# OTP3.net
KiCad netlist of a schematic drawn in Altium Designer
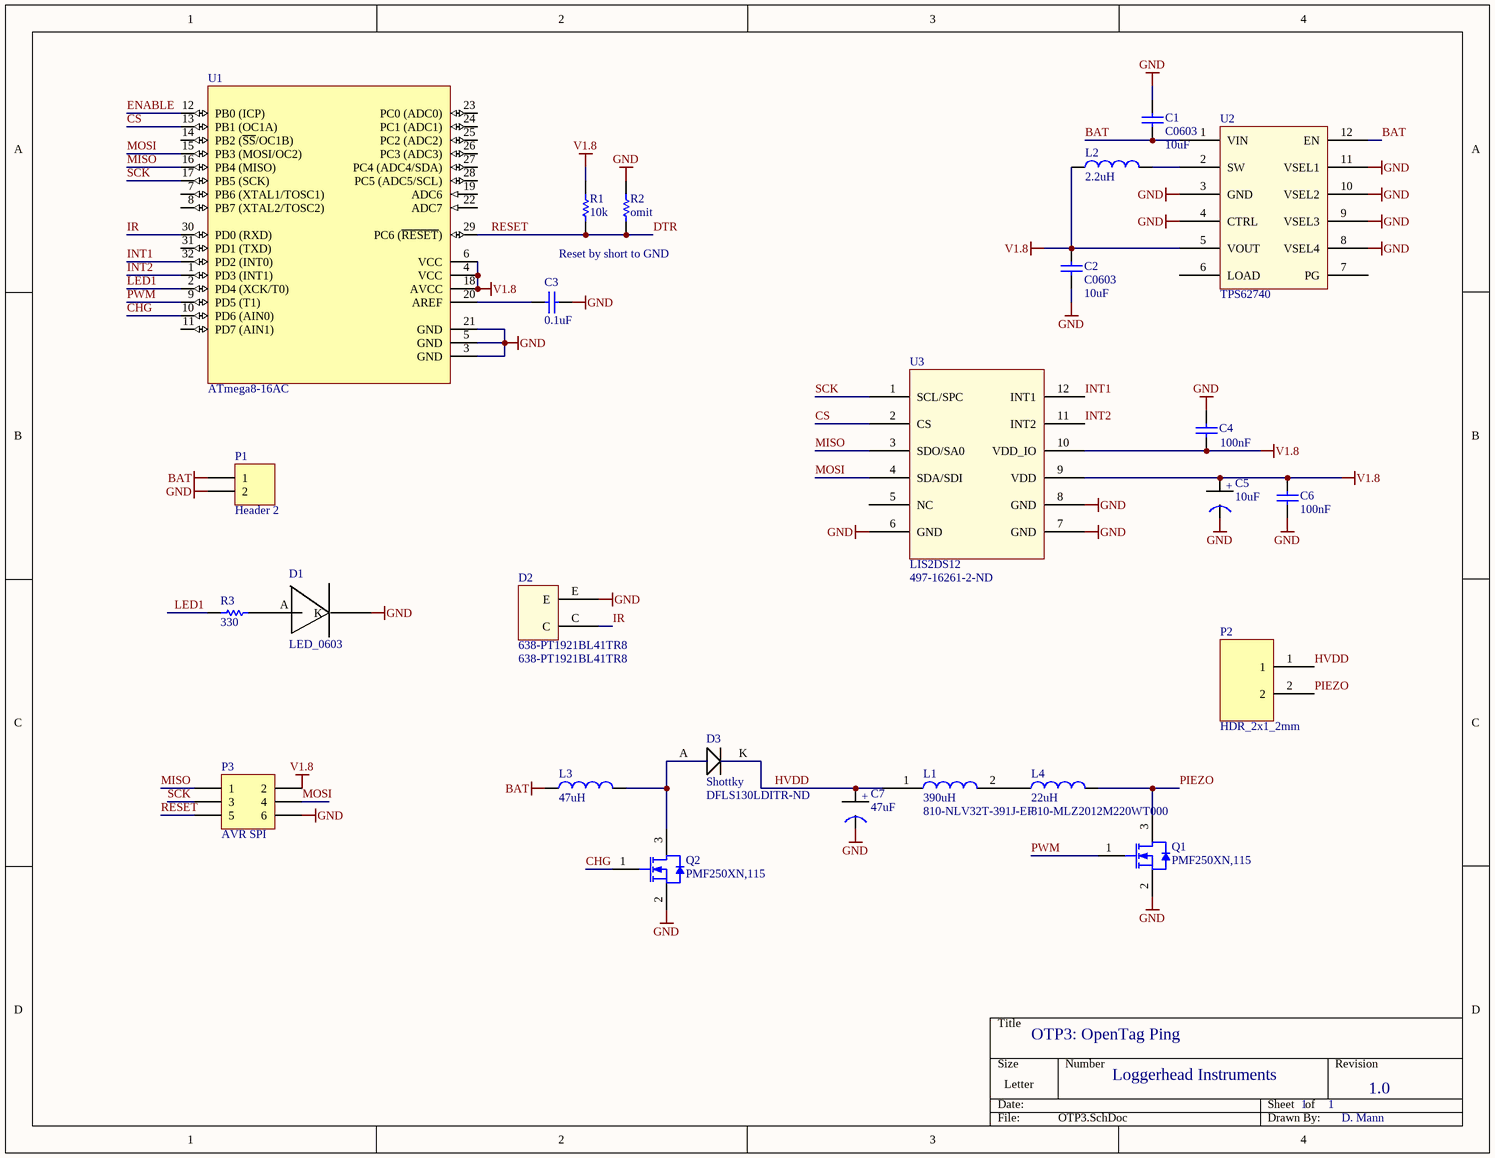
[diagram p0: OTP3.SchDoc]

(export (version "E")
  (design (tool "Eeschema 10.0.6"))
  (components
    (comp (ref "C1")
      (value "C0603")
      (footprint "0603")
      (description "Ceramic Chip Capacitor - Standard")
      (fields (field (name "ALTIUM_VALUE") "10uF") (field (name "PUBLISHER") "Altium Limited"))
      (libsource (lib "KEMET Chip Capacitor") (part "C0603"))
    )
    (comp (ref "C2")
      (value "C0603")
      (footprint "0603")
      (description "Ceramic Chip Capacitor - Standard")
      (fields (field (name "ALTIUM_VALUE") "10uF") (field (name "PUBLISHER") "Altium Limited"))
      (libsource (lib "KEMET Chip Capacitor") (part "C0603"))
    )
    (comp (ref "C3")
      (value "0.1uF")
      (footprint "0402")
      (description "Ceramic Chip Capacitor - Standard")
      (fields (field (name "PUBLISHER") "Altium Limited"))
      (libsource (lib "KEMET Chip Capacitor") (part "C0402"))
    )
    (comp (ref "C4")
      (value "100nF")
      (footprint "0402")
      (description "Ceramic Chip Capacitor - Standard")
      (fields (field (name "PUBLISHER") "Altium Limited"))
      (libsource (lib "KEMET Chip Capacitor") (part "C0402"))
    )
    (comp (ref "C5") (value "10uF") (footprint "Tant0805") (libsource (lib "Loggerhead") (part "Tant0805")))
    (comp (ref "C6")
      (value "100nF")
      (footprint "0402")
      (description "Ceramic Chip Capacitor - Standard")
      (fields (field (name "PUBLISHER") "Altium Limited"))
      (libsource (lib "KEMET Chip Capacitor") (part "C0402"))
    )
    (comp (ref "C7") (value "47uF") (footprint "Tant0805") (libsource (lib "Loggerhead") (part "Tant0805")))
    (comp (ref "D1")
      (value "LED_0603")
      (footprint "Diode0603")
      (libsource (lib "Loggerhead") (part "LED_0603"))
    )
    (comp (ref "D2")
      (value "638-PT1921BL41TR8")
      (footprint "Phototransistor")
      (description "Phototransistor")
      (fields (field (name "SUPPLIER PART NUMBER 1") "638-PT1921BL41TR8"))
      (libsource (lib "Loggerhead") (part "Phototransistor"))
    )
    (comp (ref "D3")
      (value "Shottky")
      (footprint "DFLS130")
      (fields (field (name "SUPPLIER PART NUMBER 1") "DFLS130LDITR-ND"))
      (libsource (lib "Loggerhead") (part "DFLS130"))
    )
    (comp (ref "L1")
      (value "390uH")
      (footprint "Inductor_NLV32T")
      (fields (field (name "SUPPLIER PART NUMBER 1") "810-NLV32T-391J-EF"))
      (libsource (lib "Loggerhead") (part "Inductor_NLV32T"))
    )
    (comp (ref "L2")
      (value "2.2uH")
      (footprint "Inductor KLZ1608AHR")
      (libsource (lib "Loggerhead") (part "Inductor KLZ1608"))
    )
    (comp (ref "L3")
      (value "47uH")
      (footprint "Inductor KLZ1608AHR")
      (libsource (lib "Loggerhead") (part "Inductor KLZ1608"))
    )
    (comp (ref "L4")
      (value "22uH")
      (footprint "Inductor MLZ2012M220WT000")
      (fields (field (name "SUPPLIER PART NUMBER 1") "810-MLZ2012M220WT000"))
      (libsource (lib "Loggerhead") (part "Inductor MLZ2012M220WT000"))
    )
    (comp (ref "P1")
      (value "Header 2")
      (footprint "HDR1X2")
      (description "Header, 2-Pin")
      (fields (field (name "PUBLISHER") "Altium Limited"))
      (libsource (lib "Miscellaneous Connectors") (part "Header 2"))
    )
    (comp (ref "P2")
      (value "HDR_2x1_2mm")
      (footprint "HDR_2x1_2mm")
      (libsource (lib "Loggerhead") (part "HDR_2x1_2mm"))
    )
    (comp (ref "P3")
      (value "AVR SPI")
      (footprint "HDR2X3")
      (description "Header, 3-Pin, Dual row")
      (fields (field (name "PUBLISHER") "Altium Limited"))
      (libsource (lib "Miscellaneous Connectors") (part "Header 3X2"))
    )
    (comp (ref "Q1")
      (value "PMF250XN,115")
      (footprint "NXP-SOT323_N")
      (description "N-Channel Trench MOSFET, 30 V, 0.9 A, -55 to 150 degC, 3-Pin SOT323, Tape and Reel")
      (fields (field (name "MANUFACTURER") "NXP Semiconductors"))
      (libsource (lib "NXP Semiconductors Standard MOSFETs") (part "PMF250XN,115"))
    )
    (comp (ref "Q2")
      (value "PMF250XN,115")
      (footprint "NXP-SOT323_N")
      (description "N-Channel Trench MOSFET, 30 V, 0.9 A, -55 to 150 degC, 3-Pin SOT323, Tape and Reel")
      (fields (field (name "MANUFACTURER") "NXP Semiconductors"))
      (libsource (lib "NXP Semiconductors Standard MOSFETs") (part "PMF250XN,115"))
    )
    (comp (ref "R1")
      (value "10k")
      (footprint "3-0603")
      (fields (field (name "PUBLISHER") "Altium Limited"))
      (libsource (lib "Panasonic Resistor") (part "ERJ3RK"))
    )
    (comp (ref "R2")
      (value "omit")
      (footprint "3-0603")
      (fields (field (name "PUBLISHER") "Altium Limited"))
      (libsource (lib "Panasonic Resistor") (part "ERJ3RK"))
    )
    (comp (ref "R3")
      (value "330")
      (footprint "3-0603")
      (fields (field (name "PUBLISHER") "Altium Limited"))
      (libsource (lib "Panasonic Resistor") (part "ERJ3RK"))
    )
    (comp (ref "U1")
      (value "ATmega8-16AC")
      (footprint "32M1-A_M")
      (description "8-Bit AVR Microcontroller with 8K Bytes of In-System Programmable Flash Memory")
      (fields (field (name "PUBLISHER") "Altium Limited"))
      (libsource (lib "Atmel Microcontroller 8-Bit AVR") (part "ATmega8-16AC"))
    )
    (comp (ref "U2")
      (value "TPS62740")
      (footprint "TPS6274x")
      (libsource (lib "Loggerhead") (part "TPS6274x"))
    )
    (comp (ref "U3")
      (value "LIS2DS12")
      (footprint "LGA-12")
      (fields (field (name "SUPPLIER PART NUMBER 1") "497-16261-2-ND"))
      (libsource (lib "Loggerhead") (part "LIS2DS12"))
    )
  )
  (nets
    (net (code "1") (name "/CHG") (class "Default")
      (node (ref "Q2") (pin "1") (pinfunction "G_1") (pintype "passive"))
      (node (ref "U1") (pin "10") (pinfunction "PD6_(AIN0)_10") (pintype "bidirectional"))
    )
    (net (code "2") (name "/CS") (class "Default")
      (node (ref "U1") (pin "13") (pinfunction "PB1_(OC1A)_13") (pintype "bidirectional"))
      (node (ref "U3") (pin "2") (pinfunction "CS_2") (pintype "passive"))
    )
    (net (code "3") (name "/DTR") (class "Default")
      (node (ref "P3") (pin "5") (pinfunction "5_5") (pintype "passive"))
      (node (ref "R1") (pin "1") (pinfunction "1_1") (pintype "passive"))
      (node (ref "R2") (pin "1") (pinfunction "1_1") (pintype "passive"))
      (node (ref "U1") (pin "29") (pinfunction "PC6_(~{RESET})_29") (pintype "bidirectional"))
    )
    (net (code "4") (name "/ENABLE") (class "Default")
      (node (ref "U1") (pin "12") (pinfunction "PB0_(ICP)_12") (pintype "bidirectional"))
    )
    (net (code "5") (name "/HVDD") (class "Default")
      (node (ref "C7") (pin "2") (pinfunction "+_2") (pintype "passive"))
      (node (ref "D3") (pin "K") (pintype "passive"))
      (node (ref "L1") (pin "1") (pinfunction "1_1") (pintype "passive"))
      (node (ref "P2") (pin "1") (pinfunction "1_1") (pintype "passive"))
    )
    (net (code "6") (name "/INT1") (class "Default")
      (node (ref "U1") (pin "32") (pinfunction "PD2_(INT0)_32") (pintype "bidirectional"))
      (node (ref "U3") (pin "12") (pinfunction "INT1_12") (pintype "passive"))
    )
    (net (code "7") (name "/INT2") (class "Default")
      (node (ref "U1") (pin "1") (pinfunction "PD3_(INT1)_1") (pintype "bidirectional"))
      (node (ref "U3") (pin "11") (pinfunction "INT2_11") (pintype "passive"))
    )
    (net (code "8") (name "/IR") (class "Default")
      (node (ref "D2") (pin "C") (pinfunction "C_C") (pintype "passive"))
      (node (ref "U1") (pin "30") (pinfunction "PD0_(RXD)_30") (pintype "bidirectional"))
    )
    (net (code "9") (name "/LED1") (class "Default")
      (node (ref "R3") (pin "1") (pinfunction "1_1") (pintype "passive"))
      (node (ref "U1") (pin "2") (pinfunction "PD4_(XCK/T0)_2") (pintype "bidirectional"))
    )
    (net (code "10") (name "/MISO") (class "Default")
      (node (ref "P3") (pin "1") (pinfunction "1_1") (pintype "passive"))
      (node (ref "U1") (pin "16") (pinfunction "PB4_(MISO)_16") (pintype "bidirectional"))
      (node (ref "U3") (pin "3") (pinfunction "SDO/SA0_3") (pintype "passive"))
    )
    (net (code "11") (name "/MOSI") (class "Default")
      (node (ref "P3") (pin "4") (pinfunction "4_4") (pintype "passive"))
      (node (ref "U1") (pin "15") (pinfunction "PB3_(MOSI/OC2)_15") (pintype "bidirectional"))
      (node (ref "U3") (pin "4") (pinfunction "SDA/SDI_4") (pintype "passive"))
    )
    (net (code "12") (name "/PIEZO") (class "Default")
      (node (ref "L4") (pin "2") (pinfunction "2_2") (pintype "passive"))
      (node (ref "P2") (pin "2") (pinfunction "2_2") (pintype "passive"))
      (node (ref "Q1") (pin "3") (pinfunction "D_3") (pintype "passive"))
    )
    (net (code "13") (name "/PWM") (class "Default")
      (node (ref "Q1") (pin "1") (pinfunction "G_1") (pintype "passive"))
      (node (ref "U1") (pin "9") (pinfunction "PD5_(T1)_9") (pintype "bidirectional"))
    )
    (net (code "14") (name "/SCK") (class "Default")
      (node (ref "P3") (pin "3") (pinfunction "3_3") (pintype "passive"))
      (node (ref "U1") (pin "17") (pinfunction "PB5_(SCK)_17") (pintype "bidirectional"))
      (node (ref "U3") (pin "1") (pinfunction "SCL/SPC_1") (pintype "passive"))
    )
    (net (code "15") (name "BAT") (class "Default")
      (node (ref "C1") (pin "1") (pinfunction "1_1") (pintype "passive"))
      (node (ref "L3") (pin "1") (pinfunction "1_1") (pintype "passive"))
      (node (ref "P1") (pin "1") (pinfunction "1_1") (pintype "passive"))
      (node (ref "U2") (pin "1") (pinfunction "VIN_1") (pintype "passive"))
      (node (ref "U2") (pin "12") (pinfunction "EN_12") (pintype "passive"))
    )
    (net (code "16") (name "GND") (class "Default")
      (node (ref "C1") (pin "2") (pinfunction "2_2") (pintype "passive"))
      (node (ref "C2") (pin "1") (pinfunction "1_1") (pintype "passive"))
      (node (ref "C3") (pin "2") (pinfunction "2_2") (pintype "passive"))
      (node (ref "C4") (pin "2") (pinfunction "2_2") (pintype "passive"))
      (node (ref "C5") (pin "1") (pinfunction "GND_1") (pintype "passive"))
      (node (ref "C6") (pin "2") (pinfunction "2_2") (pintype "passive"))
      (node (ref "C7") (pin "1") (pinfunction "GND_1") (pintype "passive"))
      (node (ref "D1") (pin "K") (pinfunction "K_K") (pintype "passive"))
      (node (ref "D2") (pin "E") (pinfunction "E_E") (pintype "passive"))
      (node (ref "P1") (pin "2") (pinfunction "2_2") (pintype "passive"))
      (node (ref "P3") (pin "6") (pinfunction "6_6") (pintype "passive"))
      (node (ref "Q1") (pin "2") (pinfunction "S_2") (pintype "passive"))
      (node (ref "Q2") (pin "2") (pinfunction "S_2") (pintype "passive"))
      (node (ref "R2") (pin "2") (pinfunction "2_2") (pintype "passive"))
      (node (ref "U1") (pin "21") (pinfunction "GND_21") (pintype "power_in"))
      (node (ref "U1") (pin "3") (pinfunction "GND_3") (pintype "power_in"))
      (node (ref "U1") (pin "5") (pinfunction "GND_5") (pintype "power_in"))
      (node (ref "U2") (pin "10") (pinfunction "VSEL2_10") (pintype "passive"))
      (node (ref "U2") (pin "11") (pinfunction "VSEL1_11") (pintype "passive"))
      (node (ref "U2") (pin "3") (pinfunction "GND_3") (pintype "passive"))
      (node (ref "U2") (pin "4") (pinfunction "CTRL_4") (pintype "passive"))
      (node (ref "U2") (pin "8") (pinfunction "VSEL4_8") (pintype "passive"))
      (node (ref "U2") (pin "9") (pinfunction "VSEL3_9") (pintype "passive"))
      (node (ref "U3") (pin "6") (pinfunction "GND_6") (pintype "passive"))
      (node (ref "U3") (pin "7") (pinfunction "GND_7") (pintype "passive"))
      (node (ref "U3") (pin "8") (pinfunction "GND_8") (pintype "passive"))
    )
    (net (code "17") (name "Net-(D1-PadA)") (class "Default")
      (node (ref "D1") (pin "A") (pinfunction "A_A") (pintype "passive"))
      (node (ref "R3") (pin "2") (pinfunction "2_2") (pintype "passive"))
    )
    (net (code "18") (name "Net-(L1-Pad2)") (class "Default")
      (node (ref "L1") (pin "2") (pinfunction "2_2") (pintype "passive"))
      (node (ref "L4") (pin "1") (pinfunction "1_1") (pintype "passive"))
    )
    (net (code "19") (name "Net-(Q2-D)") (class "Default")
      (node (ref "D3") (pin "A") (pintype "passive"))
      (node (ref "L3") (pin "2") (pinfunction "2_2") (pintype "passive"))
      (node (ref "Q2") (pin "3") (pinfunction "D_3") (pintype "passive"))
    )
    (net (code "20") (name "Net-(U1-AREF)") (class "Default")
      (node (ref "C3") (pin "1") (pinfunction "1_1") (pintype "passive"))
      (node (ref "U1") (pin "20") (pinfunction "AREF_20") (pintype "passive"))
    )
    (net (code "21") (name "Net-(U2-SW)") (class "Default")
      (node (ref "L2") (pin "2") (pinfunction "2_2") (pintype "passive"))
      (node (ref "U2") (pin "2") (pinfunction "SW_2") (pintype "passive"))
    )
    (net (code "22") (name "V1.8") (class "Default")
      (node (ref "C2") (pin "2") (pinfunction "2_2") (pintype "passive"))
      (node (ref "C4") (pin "1") (pinfunction "1_1") (pintype "passive"))
      (node (ref "C5") (pin "2") (pinfunction "+_2") (pintype "passive"))
      (node (ref "C6") (pin "1") (pinfunction "1_1") (pintype "passive"))
      (node (ref "L2") (pin "1") (pinfunction "1_1") (pintype "passive"))
      (node (ref "P3") (pin "2") (pinfunction "2_2") (pintype "passive"))
      (node (ref "R1") (pin "2") (pinfunction "2_2") (pintype "passive"))
      (node (ref "U1") (pin "18") (pinfunction "AVCC_18") (pintype "power_in"))
      (node (ref "U1") (pin "4") (pinfunction "VCC_4") (pintype "power_in"))
      (node (ref "U1") (pin "6") (pinfunction "VCC_6") (pintype "power_in"))
      (node (ref "U2") (pin "5") (pinfunction "VOUT_5") (pintype "passive"))
      (node (ref "U3") (pin "10") (pinfunction "VDD_IO_10") (pintype "passive"))
      (node (ref "U3") (pin "9") (pinfunction "VDD_9") (pintype "passive"))
    )
    (net (code "23") (name "unconnected-(U1-ADC6-Pad19)") (class "Default")
      (node (ref "U1") (pin "19") (pinfunction "ADC6_19") (pintype "input"))
    )
    (net (code "24") (name "unconnected-(U1-ADC7-Pad22)") (class "Default")
      (node (ref "U1") (pin "22") (pinfunction "ADC7_22") (pintype "input"))
    )
    (net (code "25") (name "unconnected-(U1-PB2_(~{SS}{slash}OC1B)-Pad14)") (class "Default")
      (node (ref "U1") (pin "14") (pinfunction "PB2_(~{SS}/OC1B)_14") (pintype "bidirectional"))
    )
    (net (code "26") (name "unconnected-(U1-PB6_(XTAL1{slash}TOSC1)-Pad7)") (class "Default")
      (node (ref "U1") (pin "7") (pinfunction "PB6_(XTAL1/TOSC1)_7") (pintype "bidirectional"))
    )
    (net (code "27") (name "unconnected-(U1-PB7_(XTAL2{slash}TOSC2)-Pad8)") (class "Default")
      (node (ref "U1") (pin "8") (pinfunction "PB7_(XTAL2/TOSC2)_8") (pintype "bidirectional"))
    )
    (net (code "28") (name "unconnected-(U1-PC0_(ADC0)-Pad23)") (class "Default")
      (node (ref "U1") (pin "23") (pinfunction "PC0_(ADC0)_23") (pintype "bidirectional"))
    )
    (net (code "29") (name "unconnected-(U1-PC1_(ADC1)-Pad24)") (class "Default")
      (node (ref "U1") (pin "24") (pinfunction "PC1_(ADC1)_24") (pintype "bidirectional"))
    )
    (net (code "30") (name "unconnected-(U1-PC2_(ADC2)-Pad25)") (class "Default")
      (node (ref "U1") (pin "25") (pinfunction "PC2_(ADC2)_25") (pintype "bidirectional"))
    )
    (net (code "31") (name "unconnected-(U1-PC3_(ADC3)-Pad26)") (class "Default")
      (node (ref "U1") (pin "26") (pinfunction "PC3_(ADC3)_26") (pintype "bidirectional"))
    )
    (net (code "32") (name "unconnected-(U1-PC4_(ADC4{slash}SDA)-Pad27)") (class "Default")
      (node (ref "U1") (pin "27") (pinfunction "PC4_(ADC4/SDA)_27") (pintype "bidirectional"))
    )
    (net (code "33") (name "unconnected-(U1-PC5_(ADC5{slash}SCL)-Pad28)") (class "Default")
      (node (ref "U1") (pin "28") (pinfunction "PC5_(ADC5/SCL)_28") (pintype "bidirectional"))
    )
    (net (code "34") (name "unconnected-(U1-PD1_(TXD)-Pad31)") (class "Default")
      (node (ref "U1") (pin "31") (pinfunction "PD1_(TXD)_31") (pintype "bidirectional"))
    )
    (net (code "35") (name "unconnected-(U1-PD7_(AIN1)-Pad11)") (class "Default")
      (node (ref "U1") (pin "11") (pinfunction "PD7_(AIN1)_11") (pintype "bidirectional"))
    )
    (net (code "36") (name "unconnected-(U2-LOAD-Pad6)") (class "Default")
      (node (ref "U2") (pin "6") (pinfunction "LOAD_6") (pintype "passive"))
    )
    (net (code "37") (name "unconnected-(U2-PG-Pad7)") (class "Default")
      (node (ref "U2") (pin "7") (pinfunction "PG_7") (pintype "passive"))
    )
    (net (code "38") (name "unconnected-(U3-NC-Pad5)") (class "Default")
      (node (ref "U3") (pin "5") (pinfunction "NC_5") (pintype "passive"))
    )
  )
)
